# Board_760032v2.net
KiCad netlist of a schematic drawn in EAGLE
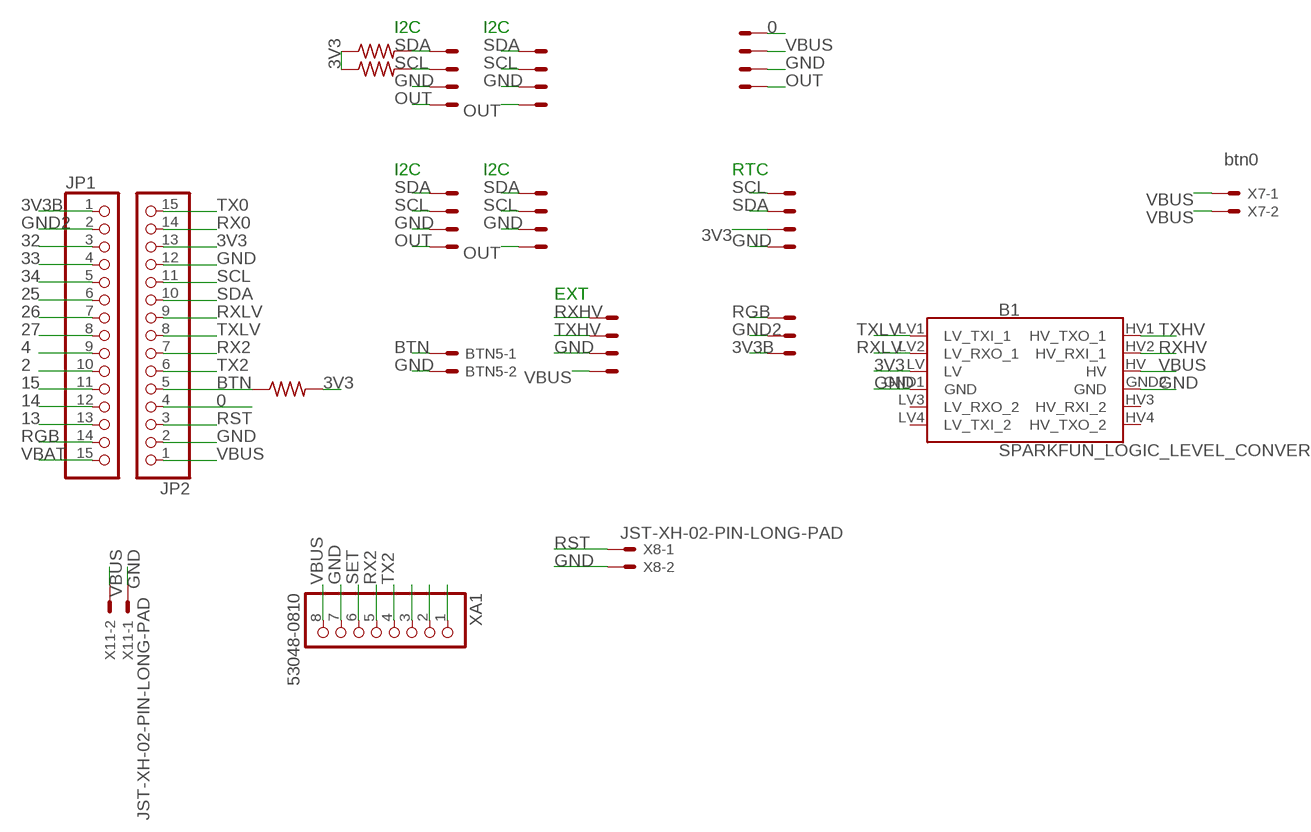
[diagram p0: schematic, sheet 1]

(export (version "E")
  (design (tool "Eeschema 10.0.6"))
  (components
    (comp (ref "B1")
      (value "SPARKFUN_LOGIC_LEVEL_CONVERTER")
      (footprint "eagle-import:SPARKFUN_LOGIC_LEVEL_CONVERTER")
      (libsource (lib "eagle-import") (part "SPARKFUN_LOGIC_LEVEL_CONVERTER"))
    )
    (comp (ref "BTN5")
      (value "JST-XH-02-PIN-LONG-PAD")
      (footprint "eagle-import:JST-XH-02-PACKAGE-LONG-PAD")
      (libsource (lib "eagle-import") (part "JST-XH-02-PIN-LONG-PAD"))
    )
    (comp (ref "JP1")
      (value "PINHD-1X15")
      (footprint "eagle-import:1X15")
      (libsource (lib "eagle-import") (part "PINHD-1X15"))
    )
    (comp (ref "JP2")
      (value "PINHD-1X15")
      (footprint "eagle-import:1X15")
      (libsource (lib "eagle-import") (part "PINHD-1X15"))
    )
    (comp (ref "R1")
      (value "R-US_0207/7")
      (footprint "eagle-import:0207_7")
      (libsource (lib "eagle-import") (part "R-US_0207/7"))
    )
    (comp (ref "R2")
      (value "R-US_0207/7")
      (footprint "eagle-import:0207_7")
      (libsource (lib "eagle-import") (part "R-US_0207/7"))
    )
    (comp (ref "R3")
      (value "R-US_0207/7")
      (footprint "eagle-import:0207_7")
      (libsource (lib "eagle-import") (part "R-US_0207/7"))
    )
    (comp (ref "RTC")
      (value "JST-XH-04-PIN-LONG-PAD")
      (footprint "eagle-import:JST-XH-04-PACKAGE-LONG-PAD")
      (libsource (lib "eagle-import") (part "JST-XH-04-PIN-LONG-PAD"))
    )
    (comp (ref "X1")
      (value "JST-XH-04-PIN-LONG-PAD")
      (footprint "eagle-import:JST-XH-04-PACKAGE-LONG-PAD")
      (libsource (lib "eagle-import") (part "JST-XH-04-PIN-LONG-PAD"))
    )
    (comp (ref "X2")
      (value "JST-XH-04-PIN-LONG-PAD")
      (footprint "eagle-import:JST-XH-04-PACKAGE-LONG-PAD")
      (libsource (lib "eagle-import") (part "JST-XH-04-PIN-LONG-PAD"))
    )
    (comp (ref "X3")
      (value "JST-XH-04-PIN-LONG-PAD")
      (footprint "eagle-import:JST-XH-04-PACKAGE-LONG-PAD")
      (libsource (lib "eagle-import") (part "JST-XH-04-PIN-LONG-PAD"))
    )
    (comp (ref "X4")
      (value "JST-XH-03-PIN-LONG-PAD")
      (footprint "eagle-import:JST-XH-03-PACKAGE-LONG-PAD")
      (libsource (lib "eagle-import") (part "JST-XH-03-PIN-LONG-PAD"))
    )
    (comp (ref "X6")
      (value "JST-XH-04-PIN-LONG-PAD")
      (footprint "eagle-import:JST-XH-04-PACKAGE-LONG-PAD")
      (libsource (lib "eagle-import") (part "JST-XH-04-PIN-LONG-PAD"))
    )
    (comp (ref "X7")
      (value "btn0")
      (footprint "eagle-import:JST-XH-02-PACKAGE-LONG-PAD")
      (libsource (lib "eagle-import") (part "JST-XH-02-PIN-LONG-PAD"))
    )
    (comp (ref "X8")
      (value "JST-XH-02-PIN-LONG-PAD")
      (footprint "eagle-import:JST-XH-02-PACKAGE-LONG-PAD")
      (libsource (lib "eagle-import") (part "JST-XH-02-PIN-LONG-PAD"))
    )
    (comp (ref "X9")
      (value "JST-XH-04-PIN-LONG-PAD")
      (footprint "eagle-import:JST-XH-04-PACKAGE-LONG-PAD")
      (libsource (lib "eagle-import") (part "JST-XH-04-PIN-LONG-PAD"))
    )
    (comp (ref "X10")
      (value "JST-XH-04-PIN-LONG-PAD")
      (footprint "eagle-import:JST-XH-04-PACKAGE-LONG-PAD")
      (libsource (lib "eagle-import") (part "JST-XH-04-PIN-LONG-PAD"))
    )
    (comp (ref "X11")
      (value "JST-XH-02-PIN-LONG-PAD")
      (footprint "eagle-import:JST-XH-02-PACKAGE-LONG-PAD")
      (libsource (lib "eagle-import") (part "JST-XH-02-PIN-LONG-PAD"))
    )
    (comp (ref "XA1")
      (value "53048-0810")
      (footprint "eagle-import:MOLEX_53048-0810")
      (fields (field (name "MF") "Molex"))
      (libsource (lib "eagle-import") (part "53048-0810"))
    )
  )
  (nets
    (net (code "1") (name "/0") (class "Default")
      (node (ref "JP2") (pin "4") (pinfunction "4_4") (pintype "passive"))
      (node (ref "X10") (pin "4") (pinfunction "S_4") (pintype "passive"))
    )
    (net (code "2") (name "/2") (class "Default")
      (node (ref "JP1") (pin "10") (pinfunction "10_10") (pintype "passive"))
    )
    (net (code "3") (name "/3V3") (class "Default")
      (node (ref "B1") (pin "LV") (pinfunction "LV_LV") (pintype "power_in"))
      (node (ref "JP2") (pin "13") (pinfunction "13_13") (pintype "passive"))
      (node (ref "R1") (pin "2") (pinfunction "2_2") (pintype "passive"))
      (node (ref "R2") (pin "1") (pinfunction "1_1") (pintype "passive"))
      (node (ref "R3") (pin "1") (pinfunction "1_1") (pintype "passive"))
      (node (ref "RTC") (pin "3") (pinfunction "S_3") (pintype "passive"))
    )
    (net (code "4") (name "/3V3B") (class "Default")
      (node (ref "JP1") (pin "1") (pinfunction "1_1") (pintype "passive"))
      (node (ref "X4") (pin "3") (pinfunction "S_3") (pintype "passive"))
    )
    (net (code "5") (name "/4") (class "Default")
      (node (ref "JP1") (pin "9") (pinfunction "9_9") (pintype "passive"))
    )
    (net (code "6") (name "/13") (class "Default")
      (node (ref "JP1") (pin "13") (pinfunction "13_13") (pintype "passive"))
    )
    (net (code "7") (name "/14") (class "Default")
      (node (ref "JP1") (pin "12") (pinfunction "12_12") (pintype "passive"))
    )
    (net (code "8") (name "/15") (class "Default")
      (node (ref "JP1") (pin "11") (pinfunction "11_11") (pintype "passive"))
    )
    (net (code "9") (name "/25") (class "Default")
      (node (ref "JP1") (pin "6") (pinfunction "6_6") (pintype "passive"))
    )
    (net (code "10") (name "/26") (class "Default")
      (node (ref "JP1") (pin "7") (pinfunction "7_7") (pintype "passive"))
    )
    (net (code "11") (name "/27") (class "Default")
      (node (ref "JP1") (pin "8") (pinfunction "8_8") (pintype "passive"))
    )
    (net (code "12") (name "/32") (class "Default")
      (node (ref "JP1") (pin "3") (pinfunction "3_3") (pintype "passive"))
    )
    (net (code "13") (name "/33") (class "Default")
      (node (ref "JP1") (pin "4") (pinfunction "4_4") (pintype "passive"))
    )
    (net (code "14") (name "/34") (class "Default")
      (node (ref "JP1") (pin "5") (pinfunction "5_5") (pintype "passive"))
    )
    (net (code "15") (name "/BTN") (class "Default")
      (node (ref "BTN5") (pin "1") (pinfunction "S_1") (pintype "passive"))
      (node (ref "JP2") (pin "5") (pinfunction "5_5") (pintype "passive"))
      (node (ref "R1") (pin "1") (pinfunction "1_1") (pintype "passive"))
    )
    (net (code "16") (name "/GND") (class "Default")
      (node (ref "B1") (pin "GND1") (pinfunction "GND_GND1") (pintype "power_in"))
      (node (ref "B1") (pin "GND2") (pinfunction "GND_GND2") (pintype "power_in"))
      (node (ref "BTN5") (pin "2") (pinfunction "S_2") (pintype "passive"))
      (node (ref "JP2") (pin "12") (pinfunction "12_12") (pintype "passive"))
      (node (ref "JP2") (pin "2") (pinfunction "2_2") (pintype "passive"))
      (node (ref "RTC") (pin "4") (pinfunction "S_4") (pintype "passive"))
      (node (ref "X1") (pin "3") (pinfunction "S_3") (pintype "passive"))
      (node (ref "X10") (pin "2") (pinfunction "S_2") (pintype "passive"))
      (node (ref "X11") (pin "1") (pinfunction "S_1") (pintype "passive"))
      (node (ref "X2") (pin "3") (pinfunction "S_3") (pintype "passive"))
      (node (ref "X3") (pin "3") (pinfunction "S_3") (pintype "passive"))
      (node (ref "X6") (pin "3") (pinfunction "S_3") (pintype "passive"))
      (node (ref "X8") (pin "2") (pinfunction "S_2") (pintype "passive"))
      (node (ref "X9") (pin "3") (pinfunction "S_3") (pintype "passive"))
      (node (ref "XA1") (pin "7") (pinfunction "7_7") (pintype "passive"))
    )
    (net (code "17") (name "/GND2") (class "Default")
      (node (ref "JP1") (pin "2") (pinfunction "2_2") (pintype "passive"))
      (node (ref "X4") (pin "2") (pinfunction "S_2") (pintype "passive"))
    )
    (net (code "18") (name "/OUT") (class "Default")
      (node (ref "X1") (pin "4") (pinfunction "S_4") (pintype "passive"))
      (node (ref "X10") (pin "1") (pinfunction "S_1") (pintype "passive"))
      (node (ref "X2") (pin "4") (pinfunction "S_4") (pintype "passive"))
      (node (ref "X3") (pin "4") (pinfunction "S_4") (pintype "passive"))
      (node (ref "X9") (pin "4") (pinfunction "S_4") (pintype "passive"))
    )
    (net (code "19") (name "/RGB") (class "Default")
      (node (ref "JP1") (pin "14") (pinfunction "14_14") (pintype "passive"))
      (node (ref "X4") (pin "1") (pinfunction "S_1") (pintype "passive"))
    )
    (net (code "20") (name "/RST") (class "Default")
      (node (ref "JP2") (pin "3") (pinfunction "3_3") (pintype "passive"))
      (node (ref "X8") (pin "1") (pinfunction "S_1") (pintype "passive"))
    )
    (net (code "21") (name "/RX0") (class "Default")
      (node (ref "JP2") (pin "14") (pinfunction "14_14") (pintype "passive"))
    )
    (net (code "22") (name "/RX2") (class "Default")
      (node (ref "JP2") (pin "7") (pinfunction "7_7") (pintype "passive"))
      (node (ref "XA1") (pin "5") (pinfunction "5_5") (pintype "passive"))
    )
    (net (code "23") (name "/RXHV") (class "Default")
      (node (ref "B1") (pin "HV2") (pinfunction "HV_RXI_1_HV2") (pintype "bidirectional"))
      (node (ref "X6") (pin "1") (pinfunction "S_1") (pintype "passive"))
    )
    (net (code "24") (name "/RXLV") (class "Default")
      (node (ref "B1") (pin "LV2") (pinfunction "LV_RXO_1_LV2") (pintype "bidirectional"))
      (node (ref "JP2") (pin "9") (pinfunction "9_9") (pintype "passive"))
    )
    (net (code "25") (name "/SCL") (class "Default")
      (node (ref "JP2") (pin "11") (pinfunction "11_11") (pintype "passive"))
      (node (ref "R3") (pin "2") (pinfunction "2_2") (pintype "passive"))
      (node (ref "RTC") (pin "1") (pinfunction "S_1") (pintype "passive"))
      (node (ref "X1") (pin "2") (pinfunction "S_2") (pintype "passive"))
      (node (ref "X2") (pin "2") (pinfunction "S_2") (pintype "passive"))
      (node (ref "X3") (pin "2") (pinfunction "S_2") (pintype "passive"))
      (node (ref "X9") (pin "2") (pinfunction "S_2") (pintype "passive"))
    )
    (net (code "26") (name "/SDA") (class "Default")
      (node (ref "JP2") (pin "10") (pinfunction "10_10") (pintype "passive"))
      (node (ref "R2") (pin "2") (pinfunction "2_2") (pintype "passive"))
      (node (ref "RTC") (pin "2") (pinfunction "S_2") (pintype "passive"))
      (node (ref "X1") (pin "1") (pinfunction "S_1") (pintype "passive"))
      (node (ref "X2") (pin "1") (pinfunction "S_1") (pintype "passive"))
      (node (ref "X3") (pin "1") (pinfunction "S_1") (pintype "passive"))
      (node (ref "X9") (pin "1") (pinfunction "S_1") (pintype "passive"))
    )
    (net (code "27") (name "/SET") (class "Default")
      (node (ref "XA1") (pin "6") (pinfunction "6_6") (pintype "passive"))
    )
    (net (code "28") (name "/TX0") (class "Default")
      (node (ref "JP2") (pin "15") (pinfunction "15_15") (pintype "passive"))
    )
    (net (code "29") (name "/TX2") (class "Default")
      (node (ref "JP2") (pin "6") (pinfunction "6_6") (pintype "passive"))
      (node (ref "XA1") (pin "4") (pinfunction "4_4") (pintype "passive"))
    )
    (net (code "30") (name "/TXHV") (class "Default")
      (node (ref "B1") (pin "HV1") (pinfunction "HV_TXO_1_HV1") (pintype "bidirectional"))
      (node (ref "X6") (pin "2") (pinfunction "S_2") (pintype "passive"))
    )
    (net (code "31") (name "/TXLV") (class "Default")
      (node (ref "B1") (pin "LV1") (pinfunction "LV_TXI_1_LV1") (pintype "bidirectional"))
      (node (ref "JP2") (pin "8") (pinfunction "8_8") (pintype "passive"))
    )
    (net (code "32") (name "/VBAT") (class "Default")
      (node (ref "JP1") (pin "15") (pinfunction "15_15") (pintype "passive"))
    )
    (net (code "33") (name "/VBUS") (class "Default")
      (node (ref "B1") (pin "HV") (pinfunction "HV_HV") (pintype "power_in"))
      (node (ref "JP2") (pin "1") (pinfunction "1_1") (pintype "passive"))
      (node (ref "X10") (pin "3") (pinfunction "S_3") (pintype "passive"))
      (node (ref "X11") (pin "2") (pinfunction "S_2") (pintype "passive"))
      (node (ref "X6") (pin "4") (pinfunction "S_4") (pintype "passive"))
      (node (ref "X7") (pin "1") (pinfunction "S_1") (pintype "passive"))
      (node (ref "X7") (pin "2") (pinfunction "S_2") (pintype "passive"))
      (node (ref "XA1") (pin "8") (pinfunction "8_8") (pintype "passive"))
    )
    (net (code "34") (name "unconnected-(B1-HV_RXI_2-PadHV3)") (class "Default")
      (node (ref "B1") (pin "HV3") (pinfunction "HV_RXI_2_HV3") (pintype "bidirectional"))
    )
    (net (code "35") (name "unconnected-(B1-HV_TXO_2-PadHV4)") (class "Default")
      (node (ref "B1") (pin "HV4") (pinfunction "HV_TXO_2_HV4") (pintype "bidirectional"))
    )
    (net (code "36") (name "unconnected-(B1-LV_RXO_2-PadLV3)") (class "Default")
      (node (ref "B1") (pin "LV3") (pinfunction "LV_RXO_2_LV3") (pintype "bidirectional"))
    )
    (net (code "37") (name "unconnected-(B1-LV_TXI_2-PadLV4)") (class "Default")
      (node (ref "B1") (pin "LV4") (pinfunction "LV_TXI_2_LV4") (pintype "bidirectional"))
    )
    (net (code "38") (name "unconnected-(XA1-Pad1)") (class "Default")
      (node (ref "XA1") (pin "1") (pinfunction "1_1") (pintype "passive"))
    )
    (net (code "39") (name "unconnected-(XA1-Pad2)") (class "Default")
      (node (ref "XA1") (pin "2") (pinfunction "2_2") (pintype "passive"))
    )
    (net (code "40") (name "unconnected-(XA1-Pad3)") (class "Default")
      (node (ref "XA1") (pin "3") (pinfunction "3_3") (pintype "passive"))
    )
  )
)
